# breakout.net
KiCad netlist of a schematic drawn in EAGLE
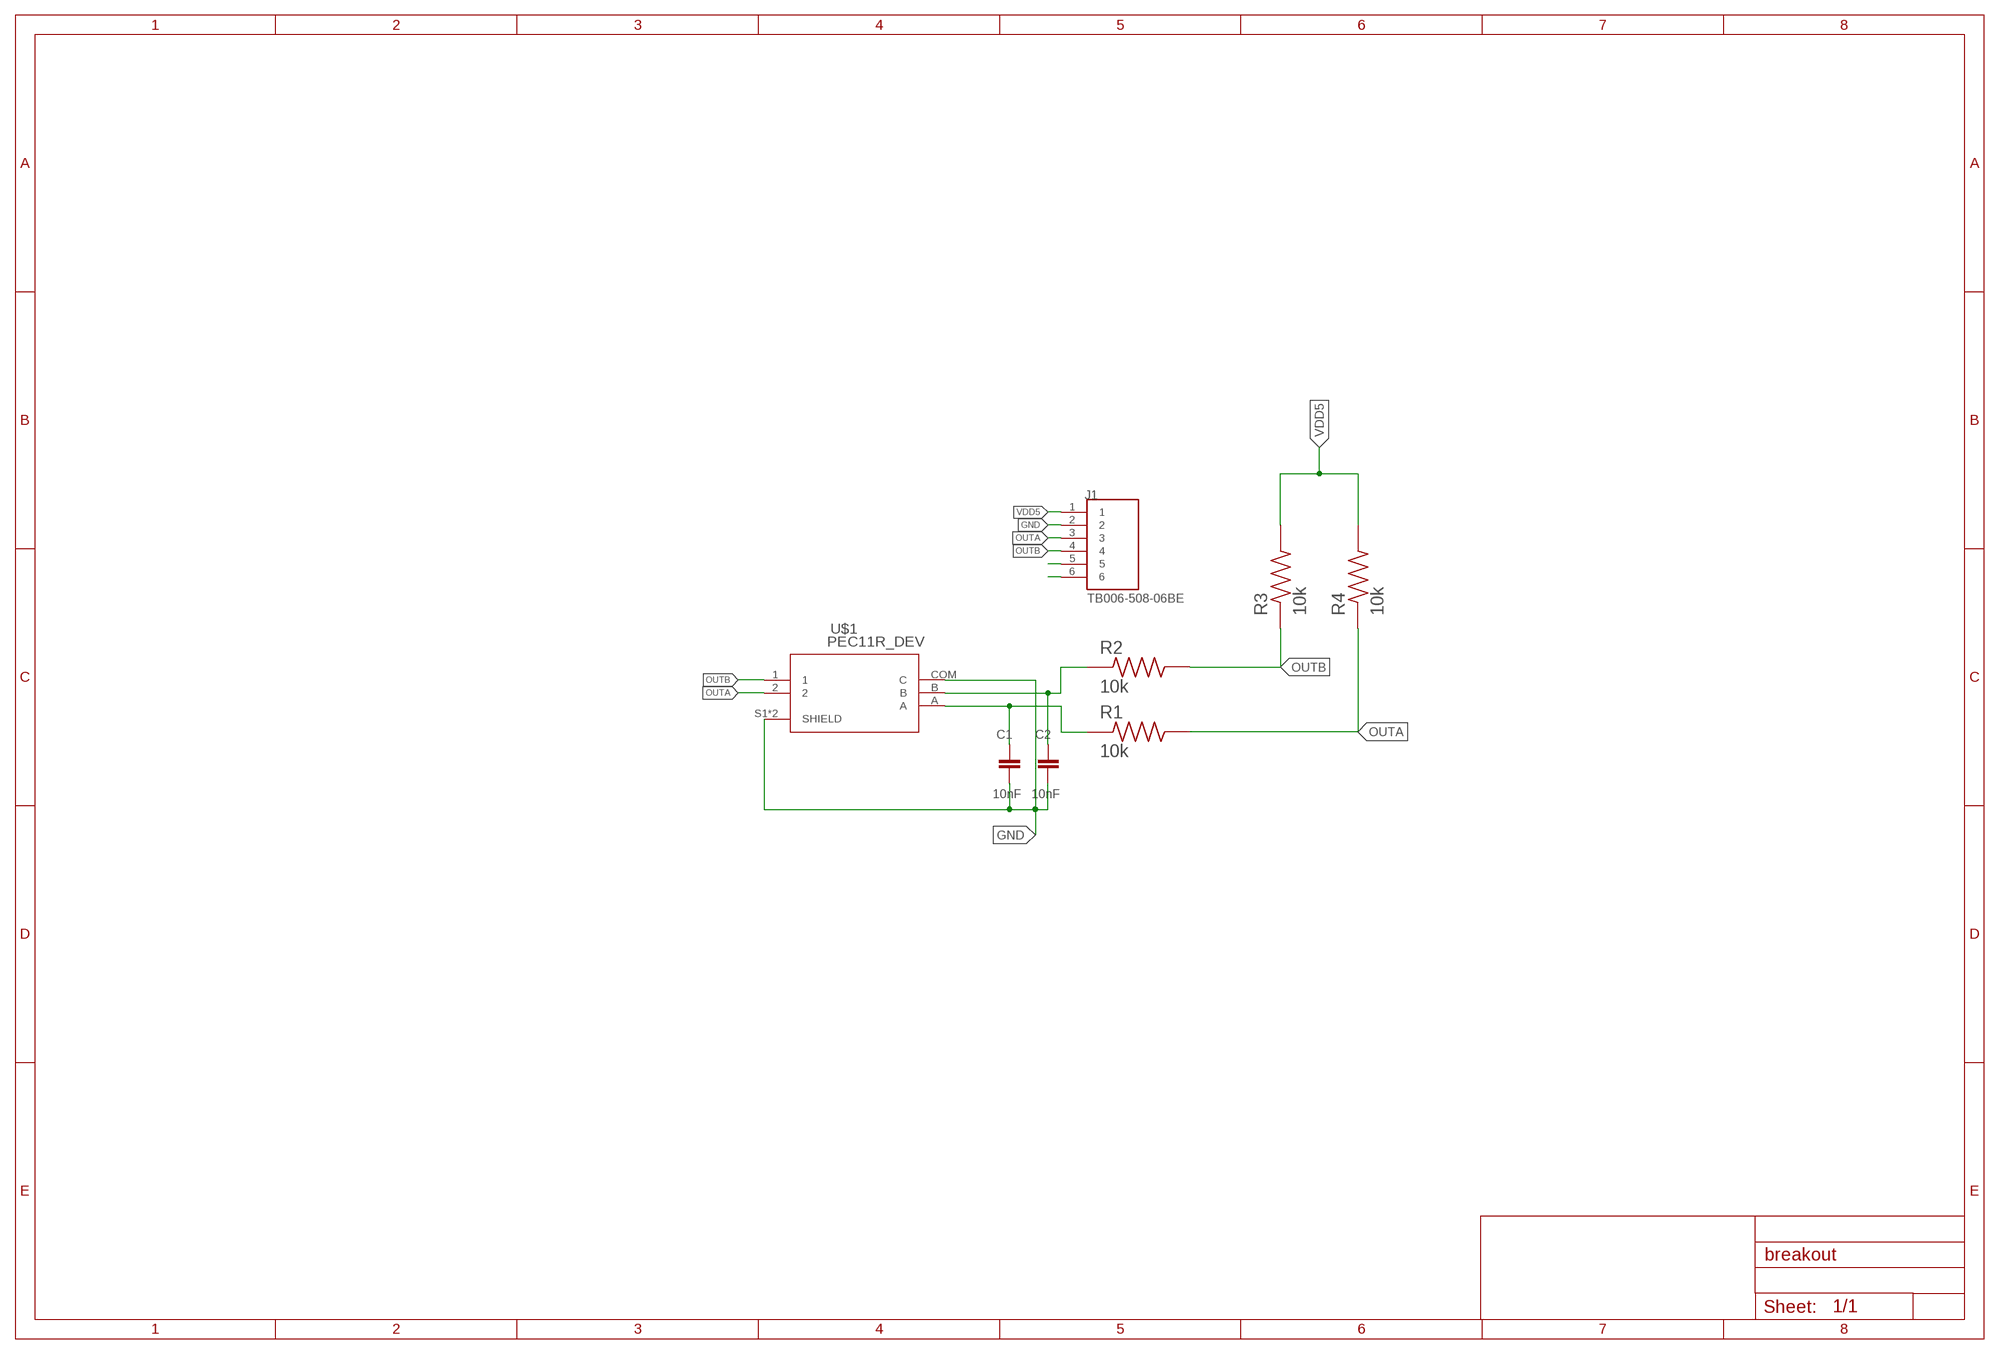
[diagram p0: schematic, sheet 1]

(export (version "E")
  (design (tool "Eeschema 10.0.6"))
  (components
    (comp (ref "C1")
      (value "10nF")
      (footprint "eagle-import:CAP_1206")
      (fields
        (field (name "DIGIKEY_PART_NUMBER") "GRM31CR60J107ME39L")
        (field (name "MANUFACTURER") "Murata Electronics North America")
        (field (name "CREATED_BY") "PCBLayout.com")
      )
      (libsource (lib "eagle-import") (part "GRM31CR60J107ME39L"))
    )
    (comp (ref "C2")
      (value "10nF")
      (footprint "eagle-import:CAP_1206")
      (fields
        (field (name "DIGIKEY_PART_NUMBER") "GRM31CR60J107ME39L")
        (field (name "MANUFACTURER") "Murata Electronics North America")
        (field (name "CREATED_BY") "PCBLayout.com")
      )
      (libsource (lib "eagle-import") (part "GRM31CR60J107ME39L"))
    )
    (comp (ref "J1")
      (value "TB006-508-06BE")
      (footprint "eagle-import:CUI_TB006-508-06BE")
      (fields (field (name "MF") "CUI Devices"))
      (libsource (lib "eagle-import") (part "TB006-508-06BE"))
    )
    (comp (ref "R1")
      (value "10k")
      (footprint "eagle-import:RESC3115X65N")
      (fields
        (field (name "COMMENT") "1-2176328-4")
        (field (name "MF") "TE Connectivity")
        (field (name "MP") "CRGP1206F120R")
      )
      (libsource (lib "eagle-import") (part "CRGP1206F120R"))
    )
    (comp (ref "R2")
      (value "10k")
      (footprint "eagle-import:RESC3115X65N")
      (fields
        (field (name "COMMENT") "1-2176328-4")
        (field (name "MF") "TE Connectivity")
        (field (name "MP") "CRGP1206F120R")
      )
      (libsource (lib "eagle-import") (part "CRGP1206F120R"))
    )
    (comp (ref "R3")
      (value "10k")
      (footprint "eagle-import:RESC3115X65N")
      (fields
        (field (name "COMMENT") "1-2176328-4")
        (field (name "MF") "TE Connectivity")
        (field (name "MP") "CRGP1206F120R")
      )
      (libsource (lib "eagle-import") (part "CRGP1206F120R"))
    )
    (comp (ref "R4")
      (value "10k")
      (footprint "eagle-import:RESC3115X65N")
      (fields
        (field (name "COMMENT") "1-2176328-4")
        (field (name "MF") "TE Connectivity")
        (field (name "MP") "CRGP1206F120R")
      )
      (libsource (lib "eagle-import") (part "CRGP1206F120R"))
    )
    (comp (ref "U$1")
      (value "PEC11R_DEV")
      (footprint "eagle-import:PEC11R_S_FP")
      (libsource (lib "eagle-import") (part "PEC11R_DEV"))
    )
  )
  (nets
    (net (code "1") (name "GND") (class "Default")
      (node (ref "C1") (pin "2") (pinfunction "2_2") (pintype "passive"))
      (node (ref "C2") (pin "2") (pinfunction "2_2") (pintype "passive"))
      (node (ref "J1") (pin "2") (pinfunction "2_2") (pintype "passive"))
      (node (ref "U$1") (pin "COM") (pinfunction "C_COM") (pintype "passive"))
      (node (ref "U$1") (pin "S1") (pinfunction "SHIELD_S1") (pintype "bidirectional"))
      (node (ref "U$1") (pin "S2") (pinfunction "SHIELD_S2") (pintype "bidirectional"))
    )
    (net (code "2") (name "Net-(C1-Pad1)") (class "Default")
      (node (ref "C1") (pin "1") (pinfunction "1_1") (pintype "passive"))
      (node (ref "R1") (pin "1") (pinfunction "1_1") (pintype "passive"))
      (node (ref "U$1") (pin "A") (pinfunction "A_A") (pintype "passive"))
    )
    (net (code "3") (name "Net-(C2-Pad1)") (class "Default")
      (node (ref "C2") (pin "1") (pinfunction "1_1") (pintype "passive"))
      (node (ref "R2") (pin "1") (pinfunction "1_1") (pintype "passive"))
      (node (ref "U$1") (pin "B") (pinfunction "B_B") (pintype "passive"))
    )
    (net (code "4") (name "OUTA") (class "Default")
      (node (ref "J1") (pin "3") (pinfunction "3_3") (pintype "passive"))
      (node (ref "R1") (pin "2") (pinfunction "2_2") (pintype "passive"))
      (node (ref "R4") (pin "1") (pinfunction "1_1") (pintype "passive"))
      (node (ref "U$1") (pin "2") (pinfunction "2_2") (pintype "passive"))
    )
    (net (code "5") (name "OUTB") (class "Default")
      (node (ref "J1") (pin "4") (pinfunction "4_4") (pintype "passive"))
      (node (ref "R2") (pin "2") (pinfunction "2_2") (pintype "passive"))
      (node (ref "R3") (pin "1") (pinfunction "1_1") (pintype "passive"))
      (node (ref "U$1") (pin "1") (pinfunction "1_1") (pintype "passive"))
    )
    (net (code "6") (name "VDD5") (class "Default")
      (node (ref "J1") (pin "1") (pinfunction "1_1") (pintype "passive"))
      (node (ref "J1") (pin "5") (pinfunction "5_5") (pintype "passive"))
      (node (ref "R3") (pin "2") (pinfunction "2_2") (pintype "passive"))
      (node (ref "R4") (pin "2") (pinfunction "2_2") (pintype "passive"))
    )
    (net (code "7") (name "unconnected-(J1-Pad6)") (class "Default")
      (node (ref "J1") (pin "6") (pinfunction "6_6") (pintype "passive"))
    )
  )
)
